# Grove_-_Mouse_Encoder_v1_0.net
KiCad netlist of a schematic drawn in EAGLE
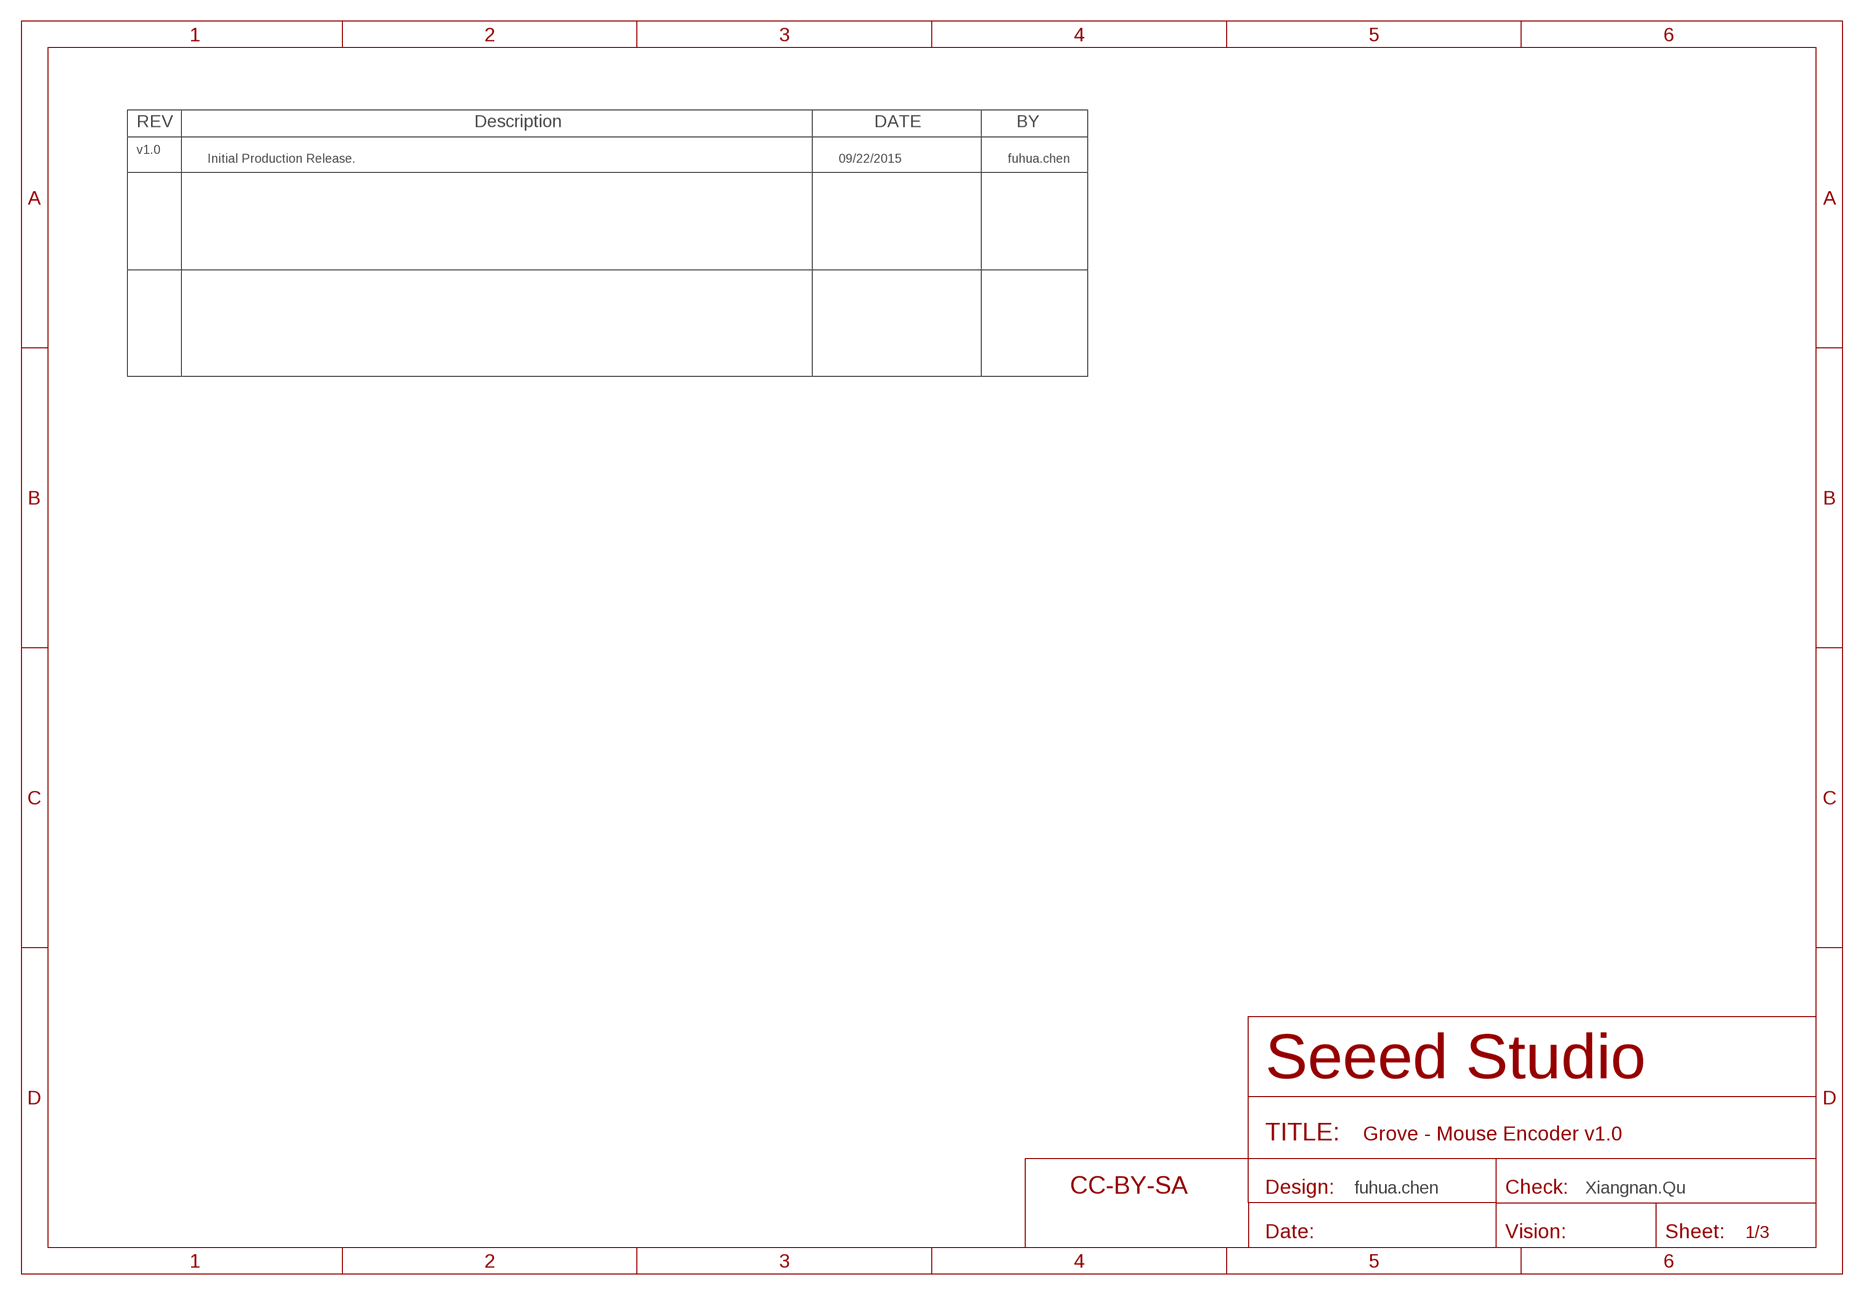
[diagram p0: schematic, sheet 1]
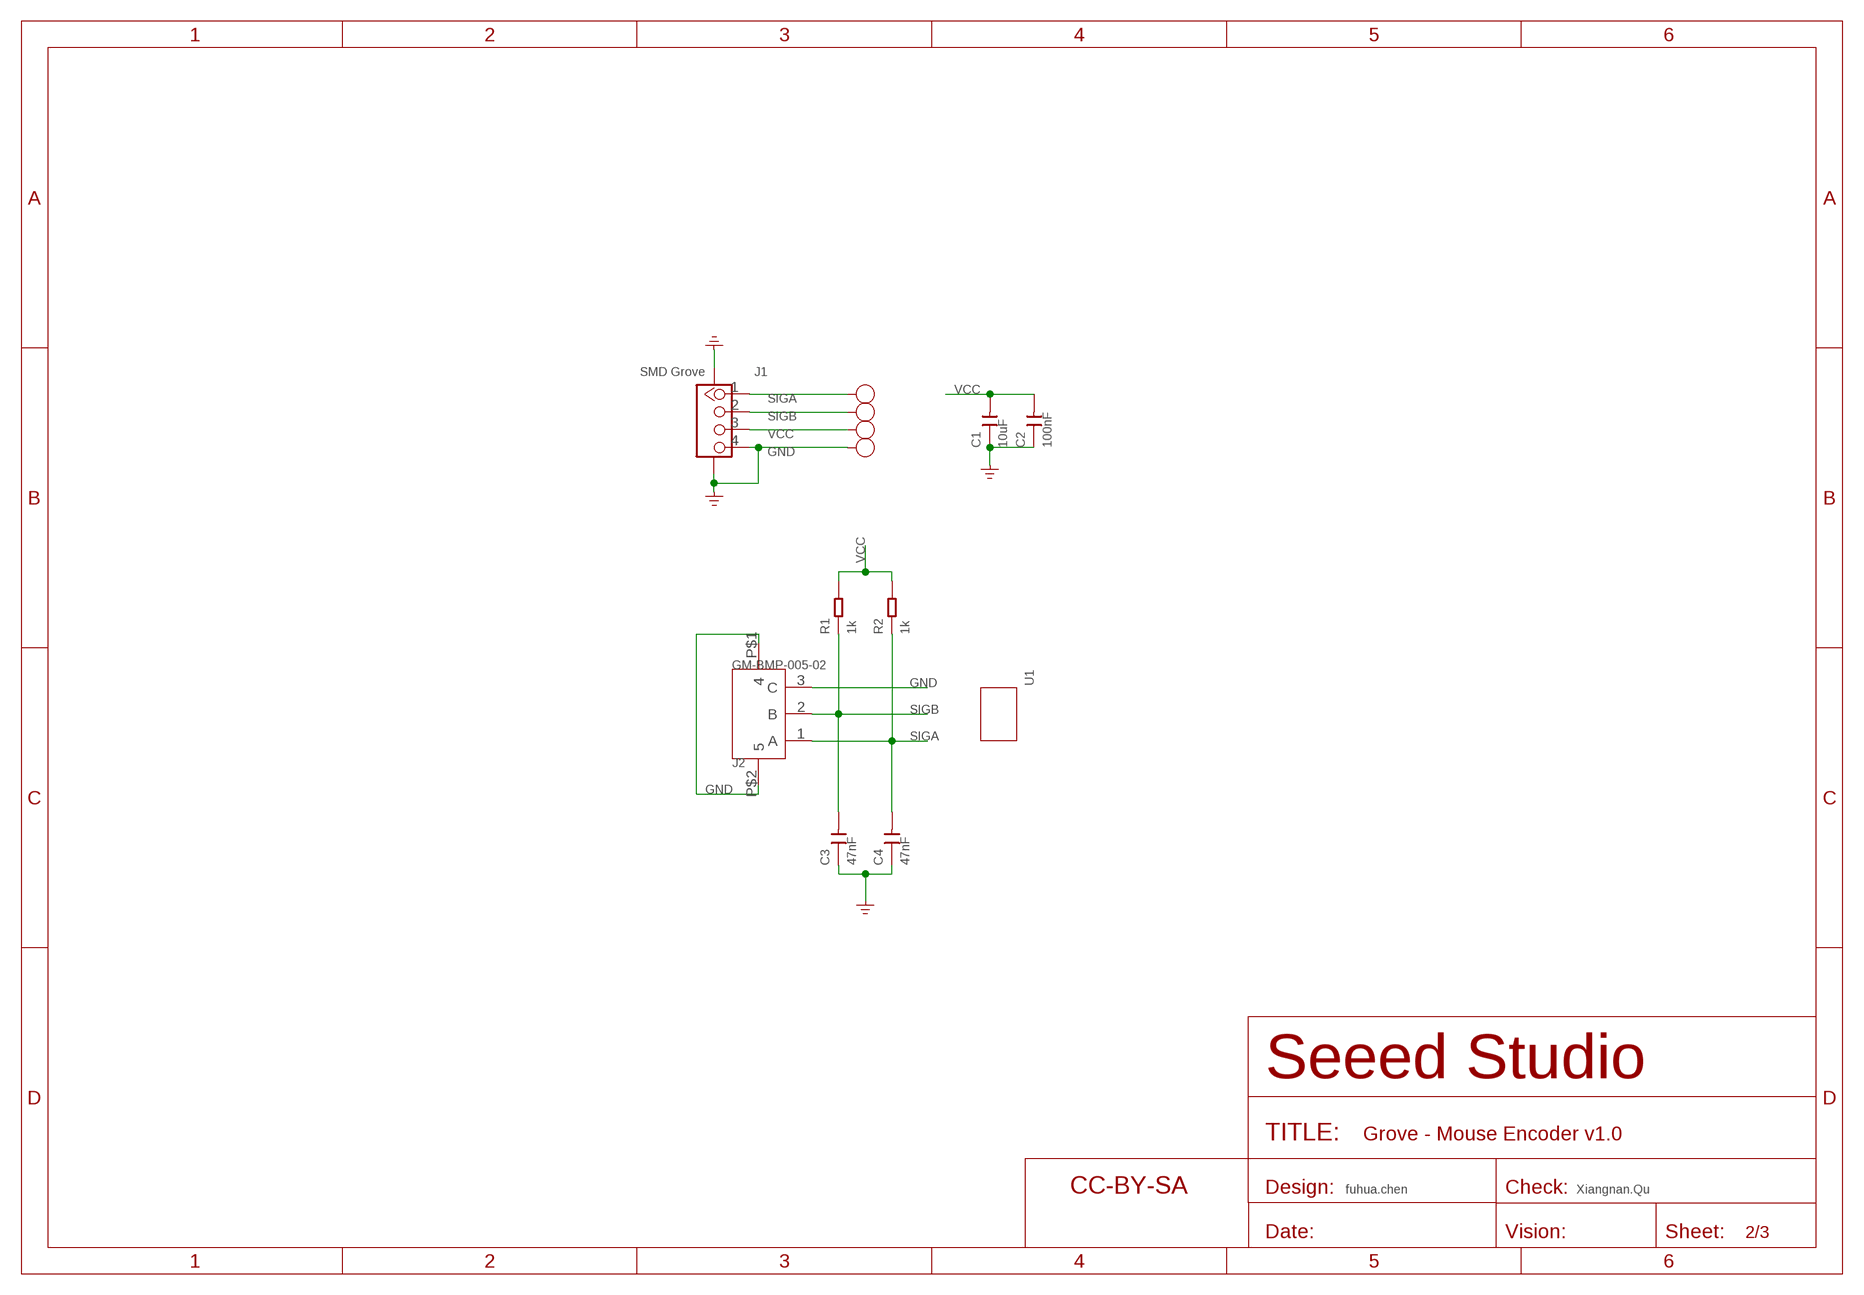
[diagram p1: schematic, sheet 2]
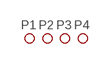
[diagram p2: schematic, sheet 3]

(export (version "E")
  (design (tool "Eeschema 10.0.6"))
  (components
    (comp (ref "C1")
      (value "10uF")
      (footprint "eagle-import:C0603")
      (libsource (lib "eagle-import") (part "CAP-0603"))
    )
    (comp (ref "C2")
      (value "100nF")
      (footprint "eagle-import:C0603")
      (libsource (lib "eagle-import") (part "CAP-0603"))
    )
    (comp (ref "C3")
      (value "47nF")
      (footprint "eagle-import:C0603")
      (libsource (lib "eagle-import") (part "CAP-0603"))
    )
    (comp (ref "C4")
      (value "47nF")
      (footprint "eagle-import:C0603")
      (libsource (lib "eagle-import") (part "CAP-0603"))
    )
    (comp (ref "FR1")
      (value "SEEEDSTUDIO-OPEN-SCH-FRAME")
      (footprint "eagle-import:SEEEDSTUDIO-PCB-FRAME")
      (libsource (lib "eagle-import") (part "SEEEDSTUDIO-OPEN-SCH-FRAME"))
    )
    (comp (ref "GND")
      (value "GND")
      (footprint "eagle-import:TP-D45MIL")
      (fields (field (name "PARTNO") "DNP"))
      (libsource (lib "eagle-import") (part "TEST-POINT'4545'"))
    )
    (comp (ref "J1")
      (value "SMD Grove")
      (footprint "eagle-import:HW4-SMD-2.0-90D")
      (libsource (lib "eagle-import") (part "GROVE-CONNECTOR-SMD'90D'"))
    )
    (comp (ref "J2")
      (value "GM-BMP-005-02")
      (footprint "eagle-import:DIP5-2.5-10.8X6.8X11.1MM")
      (libsource (lib "eagle-import") (part "ENCODER-BM002"))
    )
    (comp (ref "R1")
      (value "1k")
      (footprint "eagle-import:R0603")
      (libsource (lib "eagle-import") (part "RES-0603"))
    )
    (comp (ref "R2")
      (value "1k")
      (footprint "eagle-import:R0603")
      (libsource (lib "eagle-import") (part "RES-0603"))
    )
    (comp (ref "SIGA")
      (value "SIGA")
      (footprint "eagle-import:TP-D45MIL")
      (fields (field (name "PARTNO") "DNP"))
      (libsource (lib "eagle-import") (part "TEST-POINT'4545'"))
    )
    (comp (ref "SIGB")
      (value "SIGB")
      (footprint "eagle-import:TP-D45MIL")
      (fields (field (name "PARTNO") "DNP"))
      (libsource (lib "eagle-import") (part "TEST-POINT'4545'"))
    )
    (comp (ref "U1")
      (value "GROVE'1U'")
      (footprint "eagle-import:GROVE-1X1-TEST-PLATFORM")
      (libsource (lib "eagle-import") (part "GROVE'1U'"))
    )
    (comp (ref "VCC")
      (value "VCC")
      (footprint "eagle-import:TP-D45MIL")
      (fields (field (name "PARTNO") "DNP"))
      (libsource (lib "eagle-import") (part "TEST-POINT'4545'"))
    )
    (comp (ref "P1")
      (value "PAD-MARK'ANNULAR'")
      (footprint "eagle-import:ROUND-MARK-1.0")
      (fields (field (name "PARTNO") "DNP"))
      (libsource (lib "eagle-import") (part "PAD-MARK'ANNULAR'"))
    )
    (comp (ref "P2")
      (value "PAD-MARK'ANNULAR'")
      (footprint "eagle-import:ROUND-MARK-1.0")
      (fields (field (name "PARTNO") "DNP"))
      (libsource (lib "eagle-import") (part "PAD-MARK'ANNULAR'"))
    )
    (comp (ref "P3")
      (value "PAD-MARK'ANNULAR'")
      (footprint "eagle-import:ROUND-MARK-1.0")
      (fields (field (name "PARTNO") "DNP"))
      (libsource (lib "eagle-import") (part "PAD-MARK'ANNULAR'"))
    )
    (comp (ref "P4")
      (value "PAD-MARK'ANNULAR'")
      (footprint "eagle-import:ROUND-MARK-1.0")
      (fields (field (name "PARTNO") "DNP"))
      (libsource (lib "eagle-import") (part "PAD-MARK'ANNULAR'"))
    )
    (comp (ref "U$5")
      (value "SEEEDSTUDIO-OPEN-SCH-FRAME")
      (footprint "eagle-import:SEEEDSTUDIO-PCB-FRAME")
      (libsource (lib "eagle-import") (part "SEEEDSTUDIO-OPEN-SCH-FRAME"))
    )
  )
  (nets
    (net (code "1") (name "GND") (class "Default")
      (node (ref "C1") (pin "1") (pinfunction "1_1") (pintype "passive"))
      (node (ref "C2") (pin "1") (pinfunction "1_1") (pintype "passive"))
      (node (ref "C3") (pin "1") (pinfunction "1_1") (pintype "passive"))
      (node (ref "C4") (pin "1") (pinfunction "1_1") (pintype "passive"))
      (node (ref "GND") (pin "T") (pinfunction "T_T") (pintype "bidirectional"))
      (node (ref "J1") (pin "4") (pinfunction "4_4") (pintype "bidirectional"))
      (node (ref "J1") (pin "SS1") (pinfunction "SS1_SS1") (pintype "bidirectional"))
      (node (ref "J1") (pin "SS2") (pinfunction "SS2_SS2") (pintype "bidirectional"))
      (node (ref "J2") (pin "3") (pinfunction "C_3") (pintype "bidirectional"))
      (node (ref "J2") (pin "P$1") (pinfunction "4_P$1") (pintype "bidirectional"))
      (node (ref "J2") (pin "P$2") (pinfunction "5_P$2") (pintype "bidirectional"))
    )
    (net (code "2") (name "SIGA") (class "Default")
      (node (ref "C4") (pin "2") (pinfunction "2_2") (pintype "passive"))
      (node (ref "J1") (pin "1") (pinfunction "1_1") (pintype "bidirectional"))
      (node (ref "J2") (pin "1") (pinfunction "A_1") (pintype "bidirectional"))
      (node (ref "R2") (pin "1") (pinfunction "1_1") (pintype "passive"))
      (node (ref "SIGA") (pin "T") (pinfunction "T_T") (pintype "bidirectional"))
    )
    (net (code "3") (name "SIGB") (class "Default")
      (node (ref "C3") (pin "2") (pinfunction "2_2") (pintype "passive"))
      (node (ref "J1") (pin "2") (pinfunction "2_2") (pintype "bidirectional"))
      (node (ref "J2") (pin "2") (pinfunction "B_2") (pintype "bidirectional"))
      (node (ref "R1") (pin "1") (pinfunction "1_1") (pintype "passive"))
      (node (ref "SIGB") (pin "T") (pinfunction "T_T") (pintype "bidirectional"))
    )
    (net (code "4") (name "VCC") (class "Default")
      (node (ref "C1") (pin "2") (pinfunction "2_2") (pintype "passive"))
      (node (ref "C2") (pin "2") (pinfunction "2_2") (pintype "passive"))
      (node (ref "J1") (pin "3") (pinfunction "3_3") (pintype "bidirectional"))
      (node (ref "R1") (pin "2") (pinfunction "2_2") (pintype "passive"))
      (node (ref "R2") (pin "2") (pinfunction "2_2") (pintype "passive"))
      (node (ref "VCC") (pin "T") (pinfunction "T_T") (pintype "bidirectional"))
    )
  )
)
